# 4_Accelerometer.net
KiCad netlist of a schematic drawn in Altium Designer
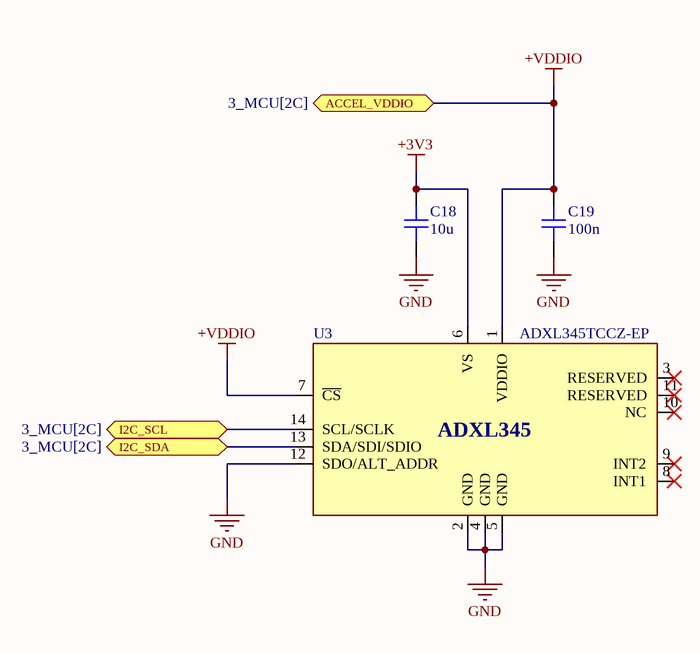
[diagram p0: 4_Accelerometer.SchDoc]

(export (version "E")
  (design (tool "Eeschema 10.0.6"))
  (components
    (comp (ref "C18")
      (value "10u")
      (footprint "CAP_0402")
      (description "Capacitor SMD 0402 10V")
      (libsource (lib "Schematic-Lib-PhilsLab") (part "CAP_0402_10V"))
    )
    (comp (ref "C19")
      (value "100n")
      (footprint "CAP_0402")
      (description "Capacitor SMD 0402 16V")
      (libsource (lib "Schematic-Lib-PhilsLab") (part "CAP_0402_16V"))
    )
    (comp (ref "U3")
      (value "ADXL345TCCZ-EP")
      (footprint "LGA_CC-14-1_ADI")
      (description "3-Axis, ±2 g/±4 g/±8 g/±16 g Digital Accelerometer Extended Performance SPI/I2C")
      (fields (field (name "MANUFACTURER") "Analog Devices"))
      (libsource (lib "Schematic-Lib-PhilsLab") (part "ADXL345TCCZ-EP"))
    )
  )
  (nets
    (net (code "1") (name "+3V3") (class "Default")
      (node (ref "C18") (pin "2") (pinfunction "2_2") (pintype "passive"))
      (node (ref "U3") (pin "6") (pinfunction "VS_6") (pintype "passive"))
    )
    (net (code "2") (name "+VDDIO") (class "Default")
      (node (ref "C19") (pin "2") (pinfunction "2_2") (pintype "passive"))
      (node (ref "U3") (pin "1") (pinfunction "VDDIO_1") (pintype "passive"))
      (node (ref "U3") (pin "7") (pinfunction "~{CS}_7") (pintype "passive"))
    )
    (net (code "3") (name "/I2C_SCL") (class "Default")
      (node (ref "U3") (pin "14") (pinfunction "SCL/SCLK_14") (pintype "passive"))
    )
    (net (code "4") (name "/I2C_SDA") (class "Default")
      (node (ref "U3") (pin "13") (pinfunction "SDA/SDI/SDIO_13") (pintype "passive"))
    )
    (net (code "5") (name "GND") (class "Default")
      (node (ref "C18") (pin "1") (pinfunction "1_1") (pintype "passive"))
      (node (ref "C19") (pin "1") (pinfunction "1_1") (pintype "passive"))
      (node (ref "U3") (pin "12") (pinfunction "SDO/ALT_ADDR_12") (pintype "passive"))
      (node (ref "U3") (pin "2") (pinfunction "GND_2") (pintype "passive"))
      (node (ref "U3") (pin "4") (pinfunction "GND_4") (pintype "passive"))
      (node (ref "U3") (pin "5") (pinfunction "GND_5") (pintype "passive"))
    )
    (net (code "6") (name "unconnected-(U3-INT1-Pad8)") (class "Default")
      (node (ref "U3") (pin "8") (pinfunction "INT1_8") (pintype "passive+no_connect"))
    )
    (net (code "7") (name "unconnected-(U3-INT2-Pad9)") (class "Default")
      (node (ref "U3") (pin "9") (pinfunction "INT2_9") (pintype "passive+no_connect"))
    )
    (net (code "8") (name "unconnected-(U3-NC-Pad10)") (class "Default")
      (node (ref "U3") (pin "10") (pinfunction "NC_10") (pintype "passive+no_connect"))
    )
    (net (code "9") (name "unconnected-(U3-RESERVED-Pad3)") (class "Default")
      (node (ref "U3") (pin "3") (pinfunction "RESERVED_3") (pintype "passive+no_connect"))
    )
    (net (code "10") (name "unconnected-(U3-RESERVED-Pad11)") (class "Default")
      (node (ref "U3") (pin "11") (pinfunction "RESERVED_11") (pintype "passive+no_connect"))
    )
  )
)
